# Sheet1a.net
KiCad netlist of a schematic drawn in Altium Designer
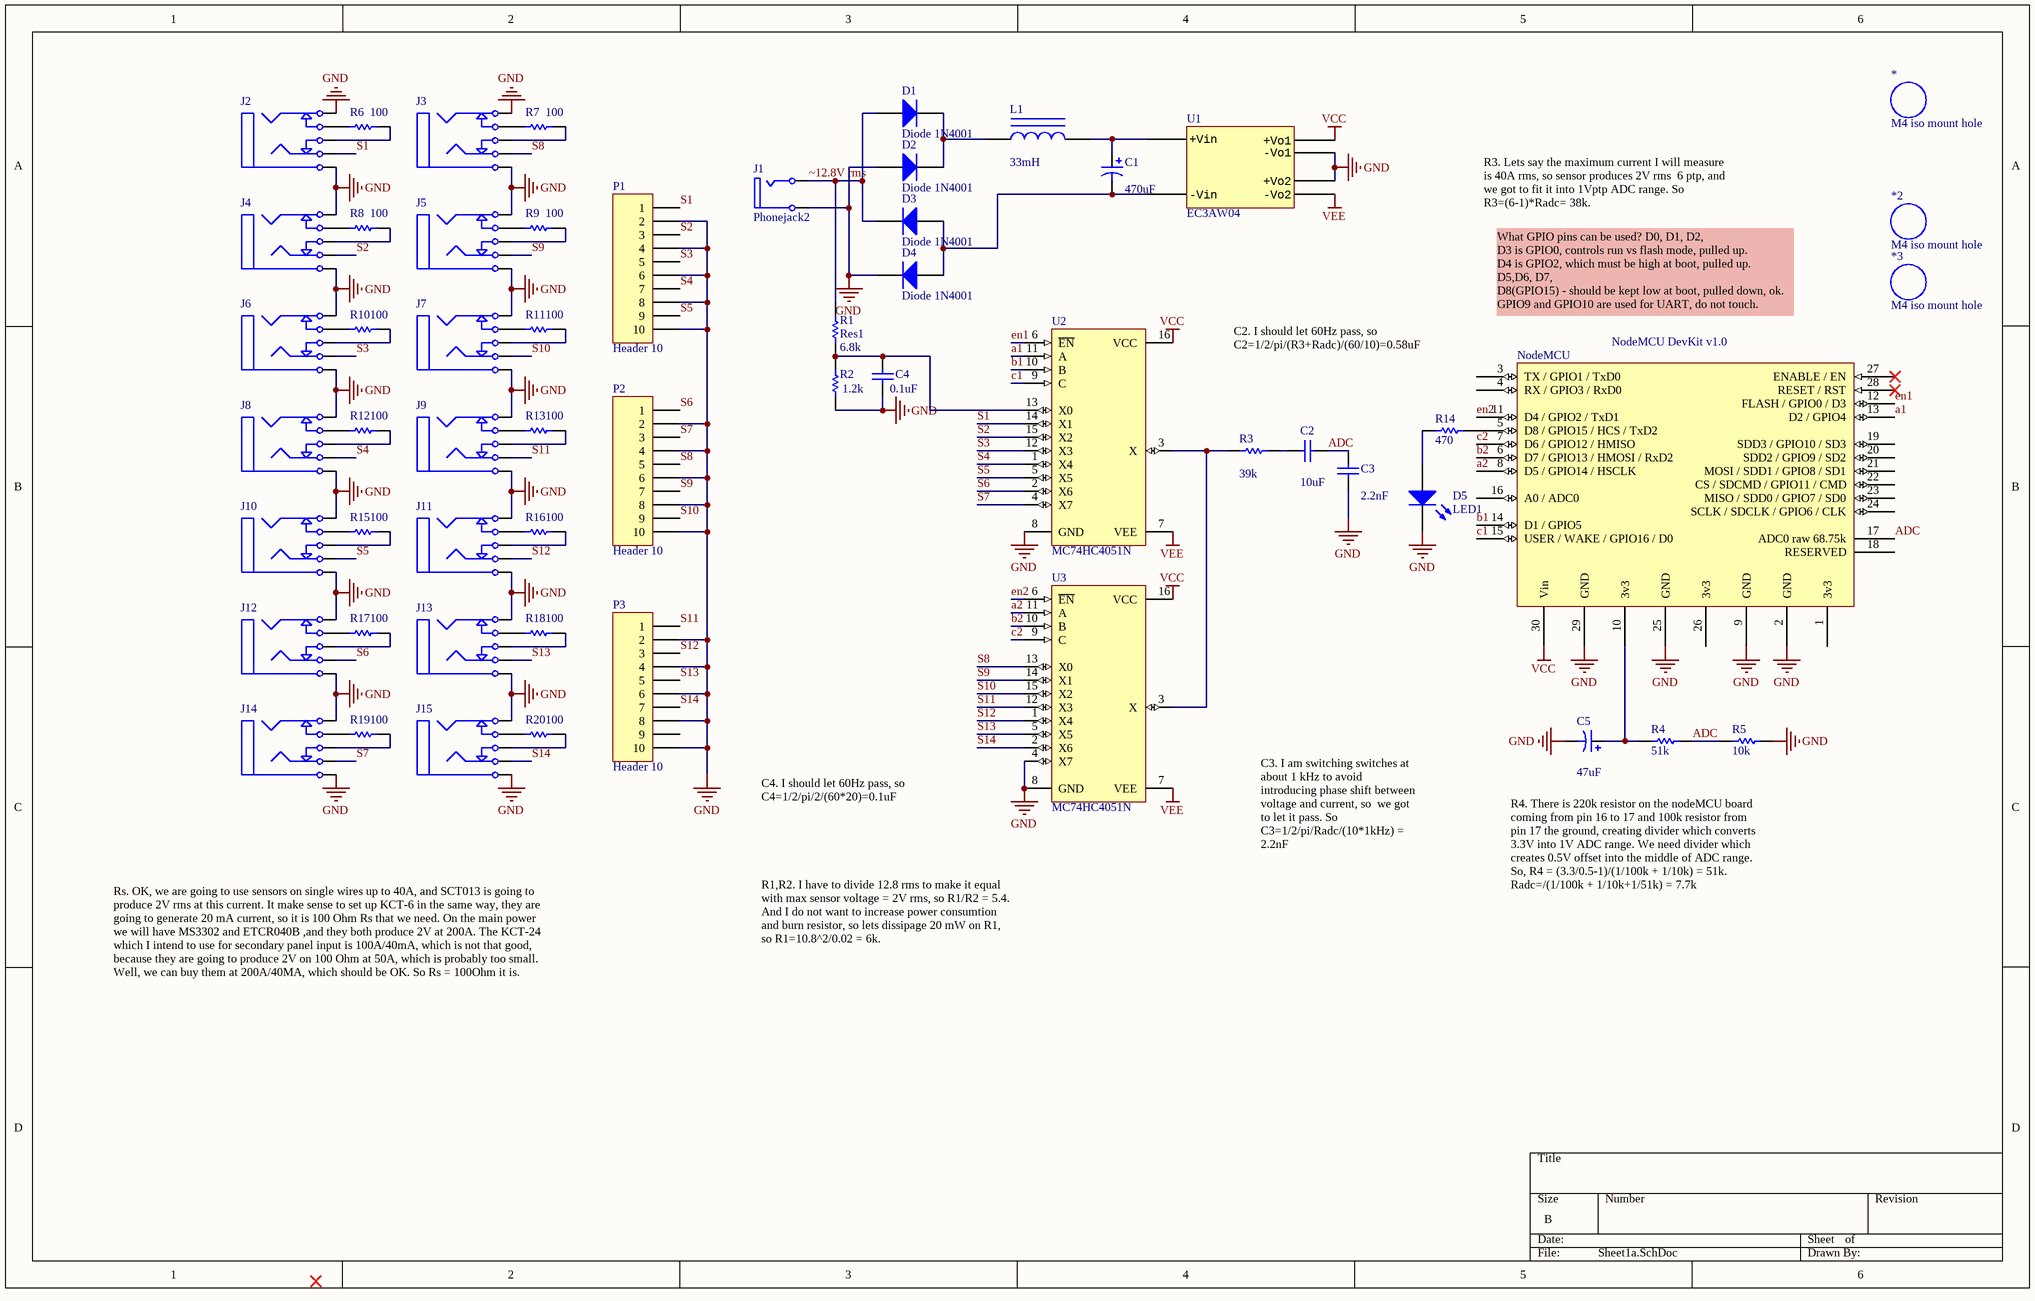
[diagram p0: Sheet1a.SchDoc]

(export (version "E")
  (design (tool "Eeschema 10.0.6"))
  (components
    (comp (ref "*")
      (value "M4 iso mount hole")
      (footprint "M4 hole")
      (libsource (lib "AVP") (part "M4 iso mount hole"))
    )
    (comp (ref "*2")
      (value "M4 iso mount hole")
      (footprint "M4 hole")
      (libsource (lib "AVP") (part "M4 iso mount hole"))
    )
    (comp (ref "*3")
      (value "M4 iso mount hole")
      (footprint "M4 hole")
      (libsource (lib "AVP") (part "M4 iso mount hole"))
    )
    (comp (ref "C1")
      (value "470uF")
      (footprint "CAPPR5-12.5x25")
      (description "Polarized Capacitor (Radial)")
      (fields (field (name "Comment") "Cap Pol1") (field (name "PUBLISHER") "Altium Limited"))
      (libsource (lib "Miscellaneous Devices") (part "Cap Pol1"))
    )
    (comp (ref "C2")
      (value "10uF")
      (footprint "RAD-0.3")
      (description "Capacitor")
      (fields (field (name "Comment") "Cap") (field (name "PUBLISHER") "Altium Limited"))
      (libsource (lib "Miscellaneous Devices") (part "Cap"))
    )
    (comp (ref "C3")
      (value "2.2nF")
      (footprint "RAD-0.3")
      (description "Capacitor")
      (fields (field (name "Comment") "Cap") (field (name "PUBLISHER") "Altium Limited"))
      (libsource (lib "Miscellaneous Devices") (part "Cap"))
    )
    (comp (ref "C4")
      (value "0.1uF")
      (footprint "RAD-0.3")
      (description "Capacitor")
      (fields (field (name "Comment") "Cap") (field (name "PUBLISHER") "Altium Limited"))
      (libsource (lib "Miscellaneous Devices") (part "Cap"))
    )
    (comp (ref "C5")
      (value "47uF")
      (footprint "CAPPR2.5-6.3x6.8/H.9")
      (description "Polarized Capacitor (Radial)")
      (fields (field (name "Comment") "Cap Pol1") (field (name "PUBLISHER") "Altium Limited"))
      (libsource (lib "Miscellaneous Devices") (part "Cap Pol1"))
    )
    (comp (ref "D1")
      (value "Diode 1N4001")
      (footprint "DO-41")
      (description "1 Amp General Purpose Rectifier")
      (fields (field (name "PUBLISHER") "Altium Limited"))
      (libsource (lib "Miscellaneous Devices") (part "Diode 1N4001"))
    )
    (comp (ref "D2")
      (value "Diode 1N4001")
      (footprint "DO-41")
      (description "1 Amp General Purpose Rectifier")
      (fields (field (name "PUBLISHER") "Altium Limited"))
      (libsource (lib "Miscellaneous Devices") (part "Diode 1N4001"))
    )
    (comp (ref "D3")
      (value "Diode 1N4001")
      (footprint "DO-41")
      (description "1 Amp General Purpose Rectifier")
      (fields (field (name "PUBLISHER") "Altium Limited"))
      (libsource (lib "Miscellaneous Devices") (part "Diode 1N4001"))
    )
    (comp (ref "D4")
      (value "Diode 1N4001")
      (footprint "DO-41")
      (description "1 Amp General Purpose Rectifier")
      (fields (field (name "PUBLISHER") "Altium Limited"))
      (libsource (lib "Miscellaneous Devices") (part "Diode 1N4001"))
    )
    (comp (ref "D5")
      (value "LED1")
      (footprint "LED-1")
      (description "Typical RED GaAs LED")
      (fields (field (name "PUBLISHER") "Altium Limited"))
      (libsource (lib "Miscellaneous Devices") (part "LED1"))
    )
    (comp (ref "J1")
      (value "Phonejack2")
      (footprint "Power jack 6x2mm")
      (description "Jack Socket, 1/4\" [6.5mm], Thru-Hole, Vertical, 2-Conductor Open Circuit")
      (fields (field (name "PUBLISHER") "Altium Limited"))
      (libsource (lib "AVP") (part "Phonejack2"))
    )
    (comp (ref "J2")
      (value "Phonejack Stereo SW")
      (footprint "SJ1-3515")
      (description "3-Conductor Jack with 2 break contacts (normals) and 2 auxiliary make contacts")
      (fields (field (name "PUBLISHER") "Altium Limited"))
      (libsource (lib "AVP") (part "Phonejack Stereo SW"))
    )
    (comp (ref "J3")
      (value "Phonejack Stereo SW")
      (footprint "SJ1-3515")
      (description "3-Conductor Jack with 2 break contacts (normals) and 2 auxiliary make contacts")
      (fields (field (name "PUBLISHER") "Altium Limited"))
      (libsource (lib "AVP") (part "Phonejack Stereo SW"))
    )
    (comp (ref "J4")
      (value "Phonejack Stereo SW")
      (footprint "SJ1-3515")
      (description "3-Conductor Jack with 2 break contacts (normals) and 2 auxiliary make contacts")
      (fields (field (name "PUBLISHER") "Altium Limited"))
      (libsource (lib "AVP") (part "Phonejack Stereo SW"))
    )
    (comp (ref "J5")
      (value "Phonejack Stereo SW")
      (footprint "SJ1-3515")
      (description "3-Conductor Jack with 2 break contacts (normals) and 2 auxiliary make contacts")
      (fields (field (name "PUBLISHER") "Altium Limited"))
      (libsource (lib "AVP") (part "Phonejack Stereo SW"))
    )
    (comp (ref "J6")
      (value "Phonejack Stereo SW")
      (footprint "SJ1-3515")
      (description "3-Conductor Jack with 2 break contacts (normals) and 2 auxiliary make contacts")
      (fields (field (name "PUBLISHER") "Altium Limited"))
      (libsource (lib "AVP") (part "Phonejack Stereo SW"))
    )
    (comp (ref "J7")
      (value "Phonejack Stereo SW")
      (footprint "SJ1-3515")
      (description "3-Conductor Jack with 2 break contacts (normals) and 2 auxiliary make contacts")
      (fields (field (name "PUBLISHER") "Altium Limited"))
      (libsource (lib "AVP") (part "Phonejack Stereo SW"))
    )
    (comp (ref "J8")
      (value "Phonejack Stereo SW")
      (footprint "SJ1-3515")
      (description "3-Conductor Jack with 2 break contacts (normals) and 2 auxiliary make contacts")
      (fields (field (name "PUBLISHER") "Altium Limited"))
      (libsource (lib "AVP") (part "Phonejack Stereo SW"))
    )
    (comp (ref "J9")
      (value "Phonejack Stereo SW")
      (footprint "SJ1-3515")
      (description "3-Conductor Jack with 2 break contacts (normals) and 2 auxiliary make contacts")
      (fields (field (name "PUBLISHER") "Altium Limited"))
      (libsource (lib "AVP") (part "Phonejack Stereo SW"))
    )
    (comp (ref "J10")
      (value "Phonejack Stereo SW")
      (footprint "SJ1-3515")
      (description "3-Conductor Jack with 2 break contacts (normals) and 2 auxiliary make contacts")
      (fields (field (name "PUBLISHER") "Altium Limited"))
      (libsource (lib "AVP") (part "Phonejack Stereo SW"))
    )
    (comp (ref "J11")
      (value "Phonejack Stereo SW")
      (footprint "SJ1-3515")
      (description "3-Conductor Jack with 2 break contacts (normals) and 2 auxiliary make contacts")
      (fields (field (name "PUBLISHER") "Altium Limited"))
      (libsource (lib "AVP") (part "Phonejack Stereo SW"))
    )
    (comp (ref "J12")
      (value "Phonejack Stereo SW")
      (footprint "SJ1-3515")
      (description "3-Conductor Jack with 2 break contacts (normals) and 2 auxiliary make contacts")
      (fields (field (name "PUBLISHER") "Altium Limited"))
      (libsource (lib "AVP") (part "Phonejack Stereo SW"))
    )
    (comp (ref "J13")
      (value "Phonejack Stereo SW")
      (footprint "SJ1-3515")
      (description "3-Conductor Jack with 2 break contacts (normals) and 2 auxiliary make contacts")
      (fields (field (name "PUBLISHER") "Altium Limited"))
      (libsource (lib "AVP") (part "Phonejack Stereo SW"))
    )
    (comp (ref "J14")
      (value "Phonejack Stereo SW")
      (footprint "SJ1-3515")
      (description "3-Conductor Jack with 2 break contacts (normals) and 2 auxiliary make contacts")
      (fields (field (name "PUBLISHER") "Altium Limited"))
      (libsource (lib "AVP") (part "Phonejack Stereo SW"))
    )
    (comp (ref "J15")
      (value "Phonejack Stereo SW")
      (footprint "SJ1-3515")
      (description "3-Conductor Jack with 2 break contacts (normals) and 2 auxiliary make contacts")
      (fields (field (name "PUBLISHER") "Altium Limited"))
      (libsource (lib "AVP") (part "Phonejack Stereo SW"))
    )
    (comp (ref "L1")
      (value "33mH")
      (footprint "Radial Vert Cylinder 10x19-6mm")
      (description "Magnetic-Core Inductor")
      (fields (field (name "Comment") "Inductor Iron") (field (name "PUBLISHER") "Altium Limited"))
      (libsource (lib "Miscellaneous Devices") (part "Inductor Iron"))
    )
    (comp (ref "NodeMCU")
      (value "NodeMCU DevKit v1.0")
      (footprint "NodeMCU v0.9")
      (libsource (lib "NodeMCU") (part "NodeMCU DevKit v1.0"))
    )
    (comp (ref "P1")
      (value "Header 10")
      (footprint "Spring Terminal")
      (description "Header, 10-Pin")
      (fields (field (name "PUBLISHER") "Altium Limited"))
      (libsource (lib "Miscellaneous Connectors") (part "Header 10"))
    )
    (comp (ref "P2")
      (value "Header 10")
      (footprint "Spring Terminal")
      (description "Header, 10-Pin")
      (fields (field (name "PUBLISHER") "Altium Limited"))
      (libsource (lib "Miscellaneous Connectors") (part "Header 10"))
    )
    (comp (ref "P3")
      (value "Header 10")
      (footprint "Spring Terminal")
      (description "Header, 10-Pin")
      (fields (field (name "PUBLISHER") "Altium Limited"))
      (libsource (lib "Miscellaneous Connectors") (part "Header 10"))
    )
    (comp (ref "R1")
      (value "Res1")
      (footprint "AXIAL-0.3")
      (description "Resistor")
      (fields (field (name "ALTIUM_VALUE") "6.8k") (field (name "PUBLISHER") "Altium Limited"))
      (libsource (lib "Miscellaneous Devices") (part "Res1"))
    )
    (comp (ref "R2")
      (value "1.2k")
      (footprint "AXIAL-0.3")
      (description "Resistor")
      (fields (field (name "Comment") "Res1") (field (name "PUBLISHER") "Altium Limited"))
      (libsource (lib "Miscellaneous Devices") (part "Res1"))
    )
    (comp (ref "R3")
      (value "39k")
      (footprint "AXIAL-0.3")
      (description "Resistor")
      (fields (field (name "Comment") "Res1") (field (name "PUBLISHER") "Altium Limited"))
      (libsource (lib "Miscellaneous Devices") (part "Res1"))
    )
    (comp (ref "R4")
      (value "51k")
      (footprint "AXIAL-0.3")
      (description "Resistor")
      (fields (field (name "Comment") "Res1") (field (name "PUBLISHER") "Altium Limited"))
      (libsource (lib "Miscellaneous Devices") (part "Res1"))
    )
    (comp (ref "R5")
      (value "10k")
      (footprint "AXIAL-0.3")
      (description "Resistor")
      (fields (field (name "Comment") "Res1") (field (name "PUBLISHER") "Altium Limited"))
      (libsource (lib "Miscellaneous Devices") (part "Res1"))
    )
    (comp (ref "R6")
      (value "100")
      (footprint "AXIAL-0.3")
      (description "Resistor")
      (fields (field (name "Comment") "Res1") (field (name "PUBLISHER") "Altium Limited"))
      (libsource (lib "Miscellaneous Devices") (part "Res1"))
    )
    (comp (ref "R7")
      (value "100")
      (footprint "AXIAL-0.3")
      (description "Resistor")
      (fields (field (name "Comment") "Res1") (field (name "PUBLISHER") "Altium Limited"))
      (libsource (lib "Miscellaneous Devices") (part "Res1"))
    )
    (comp (ref "R8")
      (value "100")
      (footprint "AXIAL-0.3")
      (description "Resistor")
      (fields (field (name "Comment") "Res1") (field (name "PUBLISHER") "Altium Limited"))
      (libsource (lib "Miscellaneous Devices") (part "Res1"))
    )
    (comp (ref "R9")
      (value "100")
      (footprint "AXIAL-0.3")
      (description "Resistor")
      (fields (field (name "Comment") "Res1") (field (name "PUBLISHER") "Altium Limited"))
      (libsource (lib "Miscellaneous Devices") (part "Res1"))
    )
    (comp (ref "R10")
      (value "100")
      (footprint "AXIAL-0.3")
      (description "Resistor")
      (fields (field (name "Comment") "Res1") (field (name "PUBLISHER") "Altium Limited"))
      (libsource (lib "Miscellaneous Devices") (part "Res1"))
    )
    (comp (ref "R11")
      (value "100")
      (footprint "AXIAL-0.3")
      (description "Resistor")
      (fields (field (name "Comment") "Res1") (field (name "PUBLISHER") "Altium Limited"))
      (libsource (lib "Miscellaneous Devices") (part "Res1"))
    )
    (comp (ref "R12")
      (value "100")
      (footprint "AXIAL-0.3")
      (description "Resistor")
      (fields (field (name "Comment") "Res1") (field (name "PUBLISHER") "Altium Limited"))
      (libsource (lib "Miscellaneous Devices") (part "Res1"))
    )
    (comp (ref "R13")
      (value "100")
      (footprint "AXIAL-0.3")
      (description "Resistor")
      (fields (field (name "Comment") "Res1") (field (name "PUBLISHER") "Altium Limited"))
      (libsource (lib "Miscellaneous Devices") (part "Res1"))
    )
    (comp (ref "R14")
      (value "470")
      (footprint "AXIAL-0.3")
      (description "Resistor")
      (fields (field (name "Comment") "Res1") (field (name "PUBLISHER") "Altium Limited"))
      (libsource (lib "Miscellaneous Devices") (part "Res1"))
    )
    (comp (ref "R15")
      (value "100")
      (footprint "AXIAL-0.3")
      (description "Resistor")
      (fields (field (name "Comment") "Res1") (field (name "PUBLISHER") "Altium Limited"))
      (libsource (lib "Miscellaneous Devices") (part "Res1"))
    )
    (comp (ref "R16")
      (value "100")
      (footprint "AXIAL-0.3")
      (description "Resistor")
      (fields (field (name "Comment") "Res1") (field (name "PUBLISHER") "Altium Limited"))
      (libsource (lib "Miscellaneous Devices") (part "Res1"))
    )
    (comp (ref "R17")
      (value "100")
      (footprint "AXIAL-0.3")
      (description "Resistor")
      (fields (field (name "Comment") "Res1") (field (name "PUBLISHER") "Altium Limited"))
      (libsource (lib "Miscellaneous Devices") (part "Res1"))
    )
    (comp (ref "R18")
      (value "100")
      (footprint "AXIAL-0.3")
      (description "Resistor")
      (fields (field (name "Comment") "Res1") (field (name "PUBLISHER") "Altium Limited"))
      (libsource (lib "Miscellaneous Devices") (part "Res1"))
    )
    (comp (ref "R19")
      (value "100")
      (footprint "AXIAL-0.3")
      (description "Resistor")
      (fields (field (name "Comment") "Res1") (field (name "PUBLISHER") "Altium Limited"))
      (libsource (lib "Miscellaneous Devices") (part "Res1"))
    )
    (comp (ref "R20")
      (value "100")
      (footprint "AXIAL-0.3")
      (description "Resistor")
      (fields (field (name "Comment") "Res1") (field (name "PUBLISHER") "Altium Limited"))
      (libsource (lib "Miscellaneous Devices") (part "Res1"))
    )
    (comp (ref "U1") (value "EC3AW04") (footprint "EC3AW") (libsource (lib "AVP") (part "EC3AW04")))
    (comp (ref "U2")
      (value "MC74HC4051N")
      (footprint "648-08")
      (description "8-Channel Analog Multiplexer/Demultiplexer")
      (fields (field (name "PUBLISHER") "Altium Limited"))
      (libsource (lib "Sheet1") (part "MC74HC4051N"))
    )
    (comp (ref "U3")
      (value "MC74HC4051N")
      (footprint "648-08")
      (description "8-Channel Analog Multiplexer/Demultiplexer")
      (fields (field (name "PUBLISHER") "Altium Limited"))
      (libsource (lib "Sheet1") (part "MC74HC4051N"))
    )
  )
  (nets
    (net (code "1") (name "/ADC") (class "Default")
      (node (ref "C2") (pin "1") (pinfunction "1_1") (pintype "passive"))
      (node (ref "C3") (pin "2") (pinfunction "2_2") (pintype "passive"))
      (node (ref "NodeMCU") (pin "17") (pinfunction "ADC0_raw_68.75k_17") (pintype "passive"))
      (node (ref "R4") (pin "1") (pinfunction "1_1") (pintype "passive"))
      (node (ref "R5") (pin "2") (pinfunction "2_2") (pintype "passive"))
    )
    (net (code "2") (name "/S1") (class "Default")
      (node (ref "J2") (pin "2-tip") (pinfunction "2_2-tip") (pintype "passive"))
      (node (ref "P1") (pin "1") (pinfunction "1_1") (pintype "passive"))
      (node (ref "U2") (pin "14") (pinfunction "X1_14") (pintype "bidirectional"))
    )
    (net (code "3") (name "/S2") (class "Default")
      (node (ref "J4") (pin "2-tip") (pinfunction "2_2-tip") (pintype "passive"))
      (node (ref "P1") (pin "3") (pinfunction "3_3") (pintype "passive"))
      (node (ref "U2") (pin "15") (pinfunction "X2_15") (pintype "bidirectional"))
    )
    (net (code "4") (name "/S3") (class "Default")
      (node (ref "J6") (pin "2-tip") (pinfunction "2_2-tip") (pintype "passive"))
      (node (ref "P1") (pin "5") (pinfunction "5_5") (pintype "passive"))
      (node (ref "U2") (pin "12") (pinfunction "X3_12") (pintype "bidirectional"))
    )
    (net (code "5") (name "/S4") (class "Default")
      (node (ref "J8") (pin "2-tip") (pinfunction "2_2-tip") (pintype "passive"))
      (node (ref "P1") (pin "7") (pinfunction "7_7") (pintype "passive"))
      (node (ref "U2") (pin "1") (pinfunction "X4_1") (pintype "bidirectional"))
    )
    (net (code "6") (name "/S5") (class "Default")
      (node (ref "J10") (pin "2-tip") (pinfunction "2_2-tip") (pintype "passive"))
      (node (ref "P1") (pin "9") (pinfunction "9_9") (pintype "passive"))
      (node (ref "U2") (pin "5") (pinfunction "X5_5") (pintype "bidirectional"))
    )
    (net (code "7") (name "/S6") (class "Default")
      (node (ref "J12") (pin "2-tip") (pinfunction "2_2-tip") (pintype "passive"))
      (node (ref "P2") (pin "1") (pinfunction "1_1") (pintype "passive"))
      (node (ref "U2") (pin "2") (pinfunction "X6_2") (pintype "bidirectional"))
    )
    (net (code "8") (name "/S7") (class "Default")
      (node (ref "J14") (pin "2-tip") (pinfunction "2_2-tip") (pintype "passive"))
      (node (ref "P2") (pin "3") (pinfunction "3_3") (pintype "passive"))
      (node (ref "U2") (pin "4") (pinfunction "X7_4") (pintype "bidirectional"))
    )
    (net (code "9") (name "/S8") (class "Default")
      (node (ref "J3") (pin "2-tip") (pinfunction "2_2-tip") (pintype "passive"))
      (node (ref "P2") (pin "5") (pinfunction "5_5") (pintype "passive"))
      (node (ref "U3") (pin "13") (pinfunction "X0_13") (pintype "bidirectional"))
    )
    (net (code "10") (name "/S9") (class "Default")
      (node (ref "J5") (pin "2-tip") (pinfunction "2_2-tip") (pintype "passive"))
      (node (ref "P2") (pin "7") (pinfunction "7_7") (pintype "passive"))
      (node (ref "U3") (pin "14") (pinfunction "X1_14") (pintype "bidirectional"))
    )
    (net (code "11") (name "/S10") (class "Default")
      (node (ref "J7") (pin "2-tip") (pinfunction "2_2-tip") (pintype "passive"))
      (node (ref "P2") (pin "9") (pinfunction "9_9") (pintype "passive"))
      (node (ref "U3") (pin "15") (pinfunction "X2_15") (pintype "bidirectional"))
    )
    (net (code "12") (name "/S11") (class "Default")
      (node (ref "J9") (pin "2-tip") (pinfunction "2_2-tip") (pintype "passive"))
      (node (ref "P3") (pin "1") (pinfunction "1_1") (pintype "passive"))
      (node (ref "U3") (pin "12") (pinfunction "X3_12") (pintype "bidirectional"))
    )
    (net (code "13") (name "/S12") (class "Default")
      (node (ref "J11") (pin "2-tip") (pinfunction "2_2-tip") (pintype "passive"))
      (node (ref "P3") (pin "3") (pinfunction "3_3") (pintype "passive"))
      (node (ref "U3") (pin "1") (pinfunction "X4_1") (pintype "bidirectional"))
    )
    (net (code "14") (name "/S13") (class "Default")
      (node (ref "J13") (pin "2-tip") (pinfunction "2_2-tip") (pintype "passive"))
      (node (ref "P3") (pin "5") (pinfunction "5_5") (pintype "passive"))
      (node (ref "U3") (pin "5") (pinfunction "X5_5") (pintype "bidirectional"))
    )
    (net (code "15") (name "/S14") (class "Default")
      (node (ref "J15") (pin "2-tip") (pinfunction "2_2-tip") (pintype "passive"))
      (node (ref "P3") (pin "7") (pinfunction "7_7") (pintype "passive"))
      (node (ref "U3") (pin "2") (pinfunction "X6_2") (pintype "bidirectional"))
    )
    (net (code "16") (name "/a1") (class "Default")
      (node (ref "NodeMCU") (pin "13") (pinfunction "D2_/_GPIO4_13") (pintype "bidirectional"))
      (node (ref "U2") (pin "11") (pinfunction "A_11") (pintype "input"))
    )
    (net (code "17") (name "/a2") (class "Default")
      (node (ref "NodeMCU") (pin "8") (pinfunction "D5_/_GPIO14_/_HSCLK_8") (pintype "bidirectional"))
      (node (ref "U3") (pin "11") (pinfunction "A_11") (pintype "input"))
    )
    (net (code "18") (name "/b1") (class "Default")
      (node (ref "NodeMCU") (pin "14") (pinfunction "D1_/_GPIO5_14") (pintype "bidirectional"))
      (node (ref "U2") (pin "10") (pinfunction "B_10") (pintype "input"))
    )
    (net (code "19") (name "/b2") (class "Default")
      (node (ref "NodeMCU") (pin "6") (pinfunction "D7_/_GPIO13_/_HMOSI_/_RxD2_6") (pintype "bidirectional"))
      (node (ref "U3") (pin "10") (pinfunction "B_10") (pintype "input"))
    )
    (net (code "20") (name "/c1") (class "Default")
      (node (ref "NodeMCU") (pin "15") (pinfunction "USER_/_WAKE_/_GPIO16_/_D0_15") (pintype "bidirectional"))
      (node (ref "U2") (pin "9") (pinfunction "C_9") (pintype "input"))
    )
    (net (code "21") (name "/c2") (class "Default")
      (node (ref "NodeMCU") (pin "7") (pinfunction "D6_/_GPIO12_/_HMISO_7") (pintype "bidirectional"))
      (node (ref "U3") (pin "9") (pinfunction "C_9") (pintype "input"))
    )
    (net (code "22") (name "/en1") (class "Default")
      (node (ref "NodeMCU") (pin "12") (pinfunction "FLASH_/_GPIO0_/_D3_12") (pintype "bidirectional"))
      (node (ref "U2") (pin "6") (pinfunction "~{EN}_6") (pintype "input"))
    )
    (net (code "23") (name "/en2") (class "Default")
      (node (ref "NodeMCU") (pin "11") (pinfunction "D4_/_GPIO2_/_TxD1_11") (pintype "bidirectional"))
      (node (ref "U3") (pin "6") (pinfunction "~{EN}_6") (pintype "input"))
    )
    (net (code "24") (name "/~12.8V rms") (class "Default")
      (node (ref "D1") (pin "1") (pinfunction "A_1") (pintype "passive"))
      (node (ref "D3") (pin "2") (pinfunction "K_2") (pintype "passive"))
      (node (ref "J1") (pin "1") (pinfunction "T_1") (pintype "passive"))
      (node (ref "R1") (pin "2") (pinfunction "2_2") (pintype "passive"))
    )
    (net (code "25") (name "GND") (class "Default")
      (node (ref "C3") (pin "1") (pinfunction "1_1") (pintype "passive"))
      (node (ref "C4") (pin "1") (pinfunction "1_1") (pintype "passive"))
      (node (ref "C5") (pin "2") (pinfunction "2_2") (pintype "passive"))
      (node (ref "D2") (pin "1") (pinfunction "A_1") (pintype "passive"))
      (node (ref "D4") (pin "2") (pinfunction "K_2") (pintype "passive"))
      (node (ref "D5") (pin "2") (pinfunction "K_2") (pintype "passive"))
      (node (ref "J1") (pin "5") (pinfunction "S_5") (pintype "power_in"))
      (node (ref "J10") (pin "1-gnd") (pinfunction "1_1-gnd") (pintype "passive"))
      (node (ref "J10") (pin "3-mid") (pinfunction "3_3-mid") (pintype "passive"))
      (node (ref "J11") (pin "1-gnd") (pinfunction "1_1-gnd") (pintype "passive"))
      (node (ref "J11") (pin "3-mid") (pinfunction "3_3-mid") (pintype "passive"))
      (node (ref "J12") (pin "1-gnd") (pinfunction "1_1-gnd") (pintype "passive"))
      (node (ref "J12") (pin "3-mid") (pinfunction "3_3-mid") (pintype "passive"))
      (node (ref "J13") (pin "1-gnd") (pinfunction "1_1-gnd") (pintype "passive"))
      (node (ref "J13") (pin "3-mid") (pinfunction "3_3-mid") (pintype "passive"))
      (node (ref "J14") (pin "1-gnd") (pinfunction "1_1-gnd") (pintype "passive"))
      (node (ref "J14") (pin "3-mid") (pinfunction "3_3-mid") (pintype "passive"))
      (node (ref "J15") (pin "1-gnd") (pinfunction "1_1-gnd") (pintype "passive"))
      (node (ref "J15") (pin "3-mid") (pinfunction "3_3-mid") (pintype "passive"))
      (node (ref "J2") (pin "1-gnd") (pinfunction "1_1-gnd") (pintype "passive"))
      (node (ref "J2") (pin "3-mid") (pinfunction "3_3-mid") (pintype "passive"))
      (node (ref "J3") (pin "1-gnd") (pinfunction "1_1-gnd") (pintype "passive"))
      (node (ref "J3") (pin "3-mid") (pinfunction "3_3-mid") (pintype "passive"))
      (node (ref "J4") (pin "1-gnd") (pinfunction "1_1-gnd") (pintype "passive"))
      (node (ref "J4") (pin "3-mid") (pinfunction "3_3-mid") (pintype "passive"))
      (node (ref "J5") (pin "1-gnd") (pinfunction "1_1-gnd") (pintype "passive"))
      (node (ref "J5") (pin "3-mid") (pinfunction "3_3-mid") (pintype "passive"))
      (node (ref "J6") (pin "1-gnd") (pinfunction "1_1-gnd") (pintype "passive"))
      (node (ref "J6") (pin "3-mid") (pinfunction "3_3-mid") (pintype "passive"))
      (node (ref "J7") (pin "1-gnd") (pinfunction "1_1-gnd") (pintype "passive"))
      (node (ref "J7") (pin "3-mid") (pinfunction "3_3-mid") (pintype "passive"))
      (node (ref "J8") (pin "1-gnd") (pinfunction "1_1-gnd") (pintype "passive"))
      (node (ref "J8") (pin "3-mid") (pinfunction "3_3-mid") (pintype "passive"))
      (node (ref "J9") (pin "1-gnd") (pinfunction "1_1-gnd") (pintype "passive"))
      (node (ref "J9") (pin "3-mid") (pinfunction "3_3-mid") (pintype "passive"))
      (node (ref "NodeMCU") (pin "2") (pinfunction "GND_2") (pintype "power_in"))
      (node (ref "NodeMCU") (pin "25") (pinfunction "GND_25") (pintype "power_in"))
      (node (ref "NodeMCU") (pin "29") (pinfunction "GND_29") (pintype "passive"))
      (node (ref "NodeMCU") (pin "9") (pinfunction "GND_9") (pintype "power_in"))
      (node (ref "P1") (pin "10") (pinfunction "10_10") (pintype "passive"))
      (node (ref "P1") (pin "2") (pinfunction "2_2") (pintype "passive"))
      (node (ref "P1") (pin "4") (pinfunction "4_4") (pintype "passive"))
      (node (ref "P1") (pin "6") (pinfunction "6_6") (pintype "passive"))
      (node (ref "P1") (pin "8") (pinfunction "8_8") (pintype "passive"))
      (node (ref "P2") (pin "10") (pinfunction "10_10") (pintype "passive"))
      (node (ref "P2") (pin "2") (pinfunction "2_2") (pintype "passive"))
      (node (ref "P2") (pin "4") (pinfunction "4_4") (pintype "passive"))
      (node (ref "P2") (pin "6") (pinfunction "6_6") (pintype "passive"))
      (node (ref "P2") (pin "8") (pinfunction "8_8") (pintype "passive"))
      (node (ref "P3") (pin "10") (pinfunction "10_10") (pintype "passive"))
      (node (ref "P3") (pin "2") (pinfunction "2_2") (pintype "passive"))
      (node (ref "P3") (pin "4") (pinfunction "4_4") (pintype "passive"))
      (node (ref "P3") (pin "6") (pinfunction "6_6") (pintype "passive"))
      (node (ref "P3") (pin "8") (pinfunction "8_8") (pintype "passive"))
      (node (ref "R2") (pin "2") (pinfunction "2_2") (pintype "passive"))
      (node (ref "R5") (pin "1") (pinfunction "1_1") (pintype "passive"))
      (node (ref "U1") (pin "10") (pinfunction "-Vo1_10") (pintype "power_in"))
      (node (ref "U1") (pin "3") (pinfunction "+Vo2_3") (pintype "power_in"))
      (node (ref "U2") (pin "8") (pinfunction "GND_8") (pintype "power_in"))
      (node (ref "U3") (pin "4") (pinfunction "X7_4") (pintype "bidirectional"))
      (node (ref "U3") (pin "8") (pinfunction "GND_8") (pintype "power_in"))
    )
    (net (code "26") (name "Net-(C2-Pad2)") (class "Default")
      (node (ref "C2") (pin "2") (pinfunction "2_2") (pintype "passive"))
      (node (ref "R3") (pin "2") (pinfunction "2_2") (pintype "passive"))
    )
    (net (code "27") (name "Net-(C5-Pad1)") (class "Default")
      (node (ref "C5") (pin "1") (pinfunction "1_1") (pintype "passive"))
      (node (ref "NodeMCU") (pin "10") (pinfunction "3v3_10") (pintype "power_in"))
      (node (ref "R4") (pin "2") (pinfunction "2_2") (pintype "passive"))
    )
    (net (code "28") (name "Net-(D1-K)") (class "Default")
      (node (ref "D1") (pin "2") (pinfunction "K_2") (pintype "passive"))
      (node (ref "D2") (pin "2") (pinfunction "K_2") (pintype "passive"))
      (node (ref "L1") (pin "1") (pinfunction "1_1") (pintype "passive"))
    )
    (net (code "29") (name "Net-(D3-A)") (class "Default")
      (node (ref "C1") (pin "2") (pinfunction "2_2") (pintype "passive"))
      (node (ref "D3") (pin "1") (pinfunction "A_1") (pintype "passive"))
      (node (ref "D4") (pin "1") (pinfunction "A_1") (pintype "passive"))
      (node (ref "U1") (pin "12") (pinfunction "-Vin_12") (pintype "power_in"))
    )
    (net (code "30") (name "Net-(D5-A)") (class "Default")
      (node (ref "D5") (pin "1") (pinfunction "A_1") (pintype "passive"))
      (node (ref "R14") (pin "2") (pinfunction "2_2") (pintype "passive"))
    )
    (net (code "31") (name "Net-(J2-4)") (class "Default")
      (node (ref "J2") (pin "4-mid-sw") (pinfunction "4_4-mid-sw") (pintype "passive"))
      (node (ref "R6") (pin "1") (pinfunction "1_1") (pintype "passive"))
    )
    (net (code "32") (name "Net-(J2-5)") (class "Default")
      (node (ref "J2") (pin "5-tip-sw") (pinfunction "5_5-tip-sw") (pintype "passive"))
      (node (ref "R6") (pin "2") (pinfunction "2_2") (pintype "passive"))
    )
    (net (code "33") (name "Net-(J3-4)") (class "Default")
      (node (ref "J3") (pin "4-mid-sw") (pinfunction "4_4-mid-sw") (pintype "passive"))
      (node (ref "R7") (pin "1") (pinfunction "1_1") (pintype "passive"))
    )
    (net (code "34") (name "Net-(J3-5)") (class "Default")
      (node (ref "J3") (pin "5-tip-sw") (pinfunction "5_5-tip-sw") (pintype "passive"))
      (node (ref "R7") (pin "2") (pinfunction "2_2") (pintype "passive"))
    )
    (net (code "35") (name "Net-(J4-4)") (class "Default")
      (node (ref "J4") (pin "4-mid-sw") (pinfunction "4_4-mid-sw") (pintype "passive"))
      (node (ref "R8") (pin "1") (pinfunction "1_1") (pintype "passive"))
    )
    (net (code "36") (name "Net-(J4-5)") (class "Default")
      (node (ref "J4") (pin "5-tip-sw") (pinfunction "5_5-tip-sw") (pintype "passive"))
      (node (ref "R8") (pin "2") (pinfunction "2_2") (pintype "passive"))
    )
    (net (code "37") (name "Net-(J5-4)") (class "Default")
      (node (ref "J5") (pin "4-mid-sw") (pinfunction "4_4-mid-sw") (pintype "passive"))
      (node (ref "R9") (pin "1") (pinfunction "1_1") (pintype "passive"))
    )
    (net (code "38") (name "Net-(J5-5)") (class "Default")
      (node (ref "J5") (pin "5-tip-sw") (pinfunction "5_5-tip-sw") (pintype "passive"))
      (node (ref "R9") (pin "2") (pinfunction "2_2") (pintype "passive"))
    )
    (net (code "39") (name "Net-(J6-4)") (class "Default")
      (node (ref "J6") (pin "4-mid-sw") (pinfunction "4_4-mid-sw") (pintype "passive"))
      (node (ref "R10") (pin "1") (pinfunction "1_1") (pintype "passive"))
    )
    (net (code "40") (name "Net-(J6-5)") (class "Default")
      (node (ref "J6") (pin "5-tip-sw") (pinfunction "5_5-tip-sw") (pintype "passive"))
      (node (ref "R10") (pin "2") (pinfunction "2_2") (pintype "passive"))
    )
    (net (code "41") (name "Net-(J7-4)") (class "Default")
      (node (ref "J7") (pin "4-mid-sw") (pinfunction "4_4-mid-sw") (pintype "passive"))
      (node (ref "R11") (pin "1") (pinfunction "1_1") (pintype "passive"))
    )
    (net (code "42") (name "Net-(J7-5)") (class "Default")
      (node (ref "J7") (pin "5-tip-sw") (pinfunction "5_5-tip-sw") (pintype "passive"))
      (node (ref "R11") (pin "2") (pinfunction "2_2") (pintype "passive"))
    )
    (net (code "43") (name "Net-(J8-4)") (class "Default")
      (node (ref "J8") (pin "4-mid-sw") (pinfunction "4_4-mid-sw") (pintype "passive"))
      (node (ref "R12") (pin "1") (pinfunction "1_1") (pintype "passive"))
    )
    (net (code "44") (name "Net-(J8-5)") (class "Default")
      (node (ref "J8") (pin "5-tip-sw") (pinfunction "5_5-tip-sw") (pintype "passive"))
      (node (ref "R12") (pin "2") (pinfunction "2_2") (pintype "passive"))
    )
    (net (code "45") (name "Net-(J9-4)") (class "Default")
      (node (ref "J9") (pin "4-mid-sw") (pinfunction "4_4-mid-sw") (pintype "passive"))
      (node (ref "R13") (pin "1") (pinfunction "1_1") (pintype "passive"))
    )
    (net (code "46") (name "Net-(J9-5)") (class "Default")
      (node (ref "J9") (pin "5-tip-sw") (pinfunction "5_5-tip-sw") (pintype "passive"))
      (node (ref "R13") (pin "2") (pinfunction "2_2") (pintype "passive"))
    )
    (net (code "47") (name "Net-(J10-4)") (class "Default")
      (node (ref "J10") (pin "4-mid-sw") (pinfunction "4_4-mid-sw") (pintype "passive"))
      (node (ref "R15") (pin "1") (pinfunction "1_1") (pintype "passive"))
    )
    (net (code "48") (name "Net-(J10-5)") (class "Default")
      (node (ref "J10") (pin "5-tip-sw") (pinfunction "5_5-tip-sw") (pintype "passive"))
      (node (ref "R15") (pin "2") (pinfunction "2_2") (pintype "passive"))
    )
    (net (code "49") (name "Net-(J11-4)") (class "Default")
      (node (ref "J11") (pin "4-mid-sw") (pinfunction "4_4-mid-sw") (pintype "passive"))
      (node (ref "R16") (pin "1") (pinfunction "1_1") (pintype "passive"))
    )
    (net (code "50") (name "Net-(J11-5)") (class "Default")
      (node (ref "J11") (pin "5-tip-sw") (pinfunction "5_5-tip-sw") (pintype "passive"))
      (node (ref "R16") (pin "2") (pinfunction "2_2") (pintype "passive"))
    )
    (net (code "51") (name "Net-(J12-4)") (class "Default")
      (node (ref "J12") (pin "4-mid-sw") (pinfunction "4_4-mid-sw") (pintype "passive"))
      (node (ref "R17") (pin "1") (pinfunction "1_1") (pintype "passive"))
    )
    (net (code "52") (name "Net-(J12-5)") (class "Default")
      (node (ref "J12") (pin "5-tip-sw") (pinfunction "5_5-tip-sw") (pintype "passive"))
      (node (ref "R17") (pin "2") (pinfunction "2_2") (pintype "passive"))
    )
    (net (code "53") (name "Net-(J13-4)") (class "Default")
      (node (ref "J13") (pin "4-mid-sw") (pinfunction "4_4-mid-sw") (pintype "passive"))
      (node (ref "R18") (pin "1") (pinfunction "1_1") (pintype "passive"))
    )
    (net (code "54") (name "Net-(J13-5)") (class "Default")
      (node (ref "J13") (pin "5-tip-sw") (pinfunction "5_5-tip-sw") (pintype "passive"))
      (node (ref "R18") (pin "2") (pinfunction "2_2") (pintype "passive"))
    )
    (net (code "55") (name "Net-(J14-4)") (class "Default")
      (node (ref "J14") (pin "4-mid-sw") (pinfunction "4_4-mid-sw") (pintype "passive"))
      (node (ref "R19") (pin "1") (pinfunction "1_1") (pintype "passive"))
    )
    (net (code "56") (name "Net-(J14-5)") (class "Default")
      (node (ref "J14") (pin "5-tip-sw") (pinfunction "5_5-tip-sw") (pintype "passive"))
      (node (ref "R19") (pin "2") (pinfunction "2_2") (pintype "passive"))
    )
    (net (code "57") (name "Net-(J15-4)") (class "Default")
      (node (ref "J15") (pin "4-mid-sw") (pinfunction "4_4-mid-sw") (pintype "passive"))
      (node (ref "R20") (pin "1") (pinfunction "1_1") (pintype "passive"))
    )
    (net (code "58") (name "Net-(J15-5)") (class "Default")
      (node (ref "J15") (pin "5-tip-sw") (pinfunction "5_5-tip-sw") (pintype "passive"))
      (node (ref "R20") (pin "2") (pinfunction "2_2") (pintype "passive"))
    )
    (net (code "59") (name "Net-(NodeMCU-D8_{slash}_GPIO15_{slash}_HCS_{slash}_TxD2)") (class "Default")
      (node (ref "NodeMCU") (pin "5") (pinfunction "D8_/_GPIO15_/_HCS_/_TxD2_5") (pintype "bidirectional"))
      (node (ref "R14") (pin "1") (pinfunction "1_1") (pintype "passive"))
    )
    (net (code "60") (name "Net-(U1-+Vin)") (class "Default")
      (node (ref "C1") (pin "1") (pinfunction "1_1") (pintype "passive"))
      (node (ref "L1") (pin "2") (pinfunction "2_2") (pintype "passive"))
      (node (ref "U1") (pin "1") (pinfunction "+Vin_1") (pintype "power_in"))
    )
    (net (code "61") (name "Net-(U2-X)") (class "Default")
      (node (ref "R3") (pin "1") (pinfunction "1_1") (pintype "passive"))
      (node (ref "U2") (pin "3") (pinfunction "X_3") (pintype "bidirectional"))
      (node (ref "U3") (pin "3") (pinfunction "X_3") (pintype "bidirectional"))
    )
    (net (code "62") (name "Net-(U2-X0)") (class "Default")
      (node (ref "C4") (pin "2") (pinfunction "2_2") (pintype "passive"))
      (node (ref "R1") (pin "1") (pinfunction "1_1") (pintype "passive"))
      (node (ref "R2") (pin "1") (pinfunction "1_1") (pintype "passive"))
      (node (ref "U2") (pin "13") (pinfunction "X0_13") (pintype "bidirectional"))
    )
    (net (code "63") (name "VCC") (class "Default")
      (node (ref "NodeMCU") (pin "30") (pinfunction "Vin_30") (pintype "passive"))
      (node (ref "U1") (pin "11") (pinfunction "+Vo1_11") (pintype "power_in"))
      (node (ref "U2") (pin "16") (pinfunction "VCC_16") (pintype "power_in"))
      (node (ref "U3") (pin "16") (pinfunction "VCC_16") (pintype "power_in"))
    )
    (net (code "64") (name "VEE") (class "Default")
      (node (ref "U1") (pin "2") (pinfunction "-Vo2_2") (pintype "power_in"))
      (node (ref "U2") (pin "7") (pinfunction "VEE_7") (pintype "power_in"))
      (node (ref "U3") (pin "7") (pinfunction "VEE_7") (pintype "power_in"))
    )
    (net (code "65") (name "unconnected-(NodeMCU-3v3-Pad1)") (class "Default")
      (node (ref "NodeMCU") (pin "1") (pinfunction "3v3_1") (pintype "power_in"))
    )
    (net (code "66") (name "unconnected-(NodeMCU-3v3-Pad26)") (class "Default")
      (node (ref "NodeMCU") (pin "26") (pinfunction "3v3_26") (pintype "power_in"))
    )
    (net (code "67") (name "unconnected-(NodeMCU-A0_{slash}_ADC0-Pad16)") (class "Default")
      (node (ref "NodeMCU") (pin "16") (pinfunction "A0_/_ADC0_16") (pintype "bidirectional"))
    )
    (net (code "68") (name "unconnected-(NodeMCU-CS_{slash}_SDCMD_{slash}_GPIO11_{slash}_CMD-Pad22)") (class "Default")
      (node (ref "NodeMCU") (pin "22") (pinfunction "CS_/_SDCMD_/_GPIO11_/_CMD_22") (pintype "bidirectional"))
    )
    (net (code "69") (name "unconnected-(NodeMCU-ENABLE_{slash}_EN-Pad27)") (class "Default")
      (node (ref "NodeMCU") (pin "27") (pinfunction "ENABLE_/_EN_27") (pintype "input+no_connect"))
    )
    (net (code "70") (name "unconnected-(NodeMCU-MISO_{slash}_SDD0_{slash}_GPIO7_{slash}_SD0-Pad23)") (class "Default")
      (node (ref "NodeMCU") (pin "23") (pinfunction "MISO_/_SDD0_/_GPIO7_/_SD0_23") (pintype "bidirectional"))
    )
    (net (code "71") (name "unconnected-(NodeMCU-MOSI_{slash}_SDD1_{slash}_GPIO8_{slash}_SD1-Pad21)") (class "Default")
      (node (ref "NodeMCU") (pin "21") (pinfunction "MOSI_/_SDD1_/_GPIO8_/_SD1_21") (pintype "bidirectional"))
    )
    (net (code "72") (name "unconnected-(NodeMCU-RESERVED-Pad18)") (class "Default")
      (node (ref "NodeMCU") (pin "18") (pinfunction "RESERVED_18") (pintype "passive"))
    )
    (net (code "73") (name "unconnected-(NodeMCU-RESET_{slash}_RST-Pad28)") (class "Default")
      (node (ref "NodeMCU") (pin "28") (pinfunction "RESET_/_RST_28") (pintype "input+no_connect"))
    )
    (net (code "74") (name "unconnected-(NodeMCU-RX_{slash}_GPIO3_{slash}_RxD0-Pad4)") (class "Default")
      (node (ref "NodeMCU") (pin "4") (pinfunction "RX_/_GPIO3_/_RxD0_4") (pintype "bidirectional"))
    )
    (net (code "75") (name "unconnected-(NodeMCU-SCLK_{slash}_SDCLK_{slash}_GPIO6_{slash}_CLK-Pad24)") (class "Default")
      (node (ref "NodeMCU") (pin "24") (pinfunction "SCLK_/_SDCLK_/_GPIO6_/_CLK_24") (pintype "bidirectional"))
    )
    (net (code "76") (name "unconnected-(NodeMCU-SDD2_{slash}_GPIO9_{slash}_SD2-Pad20)") (class "Default")
      (node (ref "NodeMCU") (pin "20") (pinfunction "SDD2_/_GPIO9_/_SD2_20") (pintype "bidirectional"))
    )
    (net (code "77") (name "unconnected-(NodeMCU-SDD3_{slash}_GPIO10_{slash}_SD3-Pad19)") (class "Default")
      (node (ref "NodeMCU") (pin "19") (pinfunction "SDD3_/_GPIO10_/_SD3_19") (pintype "bidirectional"))
    )
    (net (code "78") (name "unconnected-(NodeMCU-TX_{slash}_GPIO1_{slash}_TxD0-Pad3)") (class "Default")
      (node (ref "NodeMCU") (pin "3") (pinfunction "TX_/_GPIO1_/_TxD0_3") (pintype "bidirectional"))
    )
    (net (code "79") (name "unconnected-(P3-Pad9)") (class "Default")
      (node (ref "P3") (pin "9") (pinfunction "9_9") (pintype "passive"))
    )
  )
)
